# Sche_Boost.net
KiCad netlist of a schematic drawn in Altium Designer
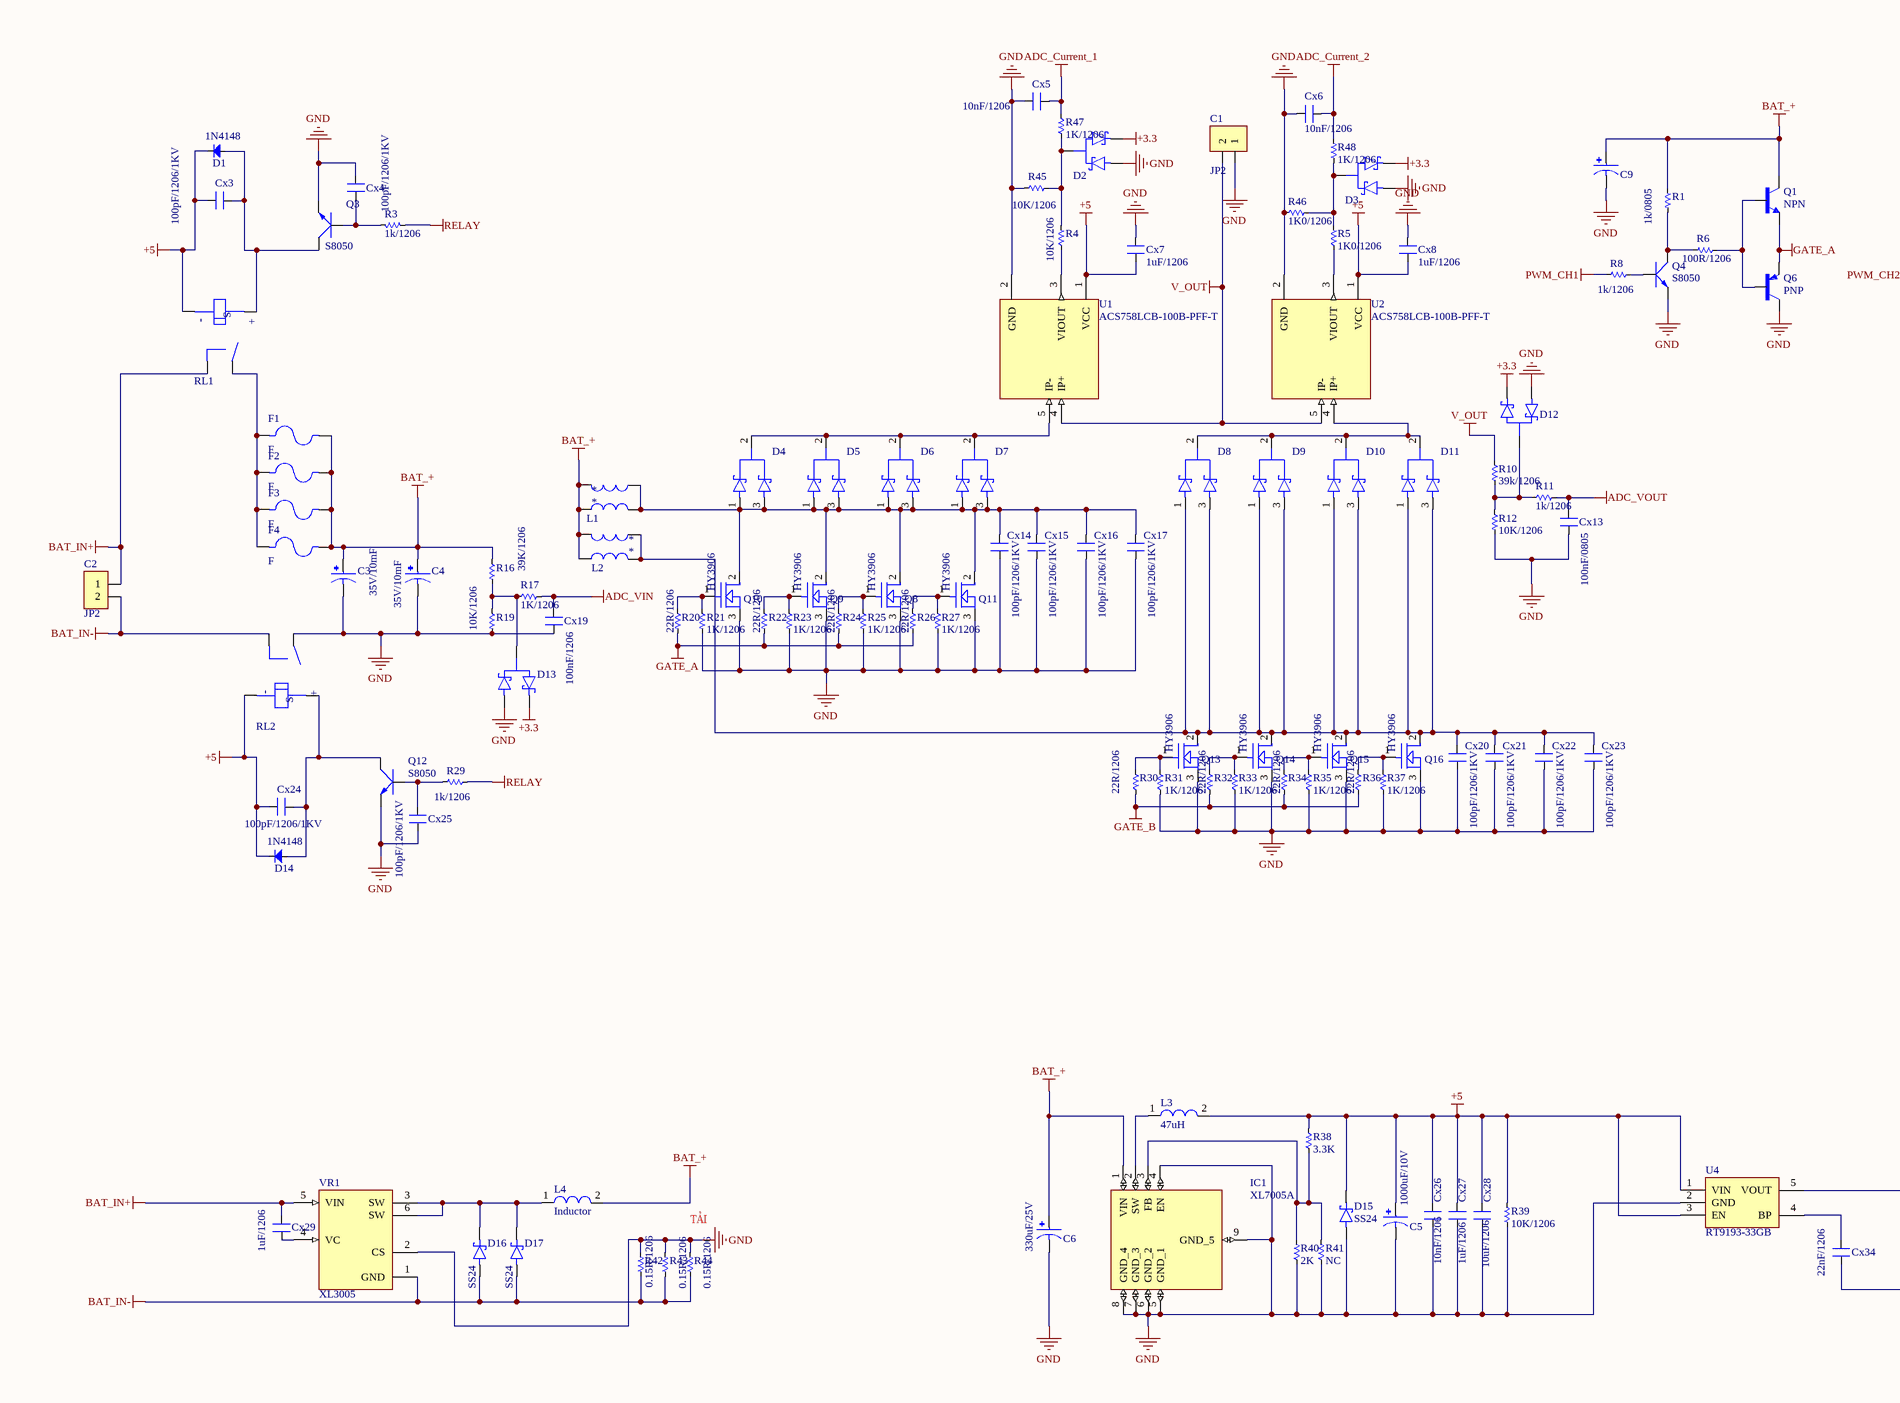
[diagram p0: Sche_Boost.SchDoc, left]
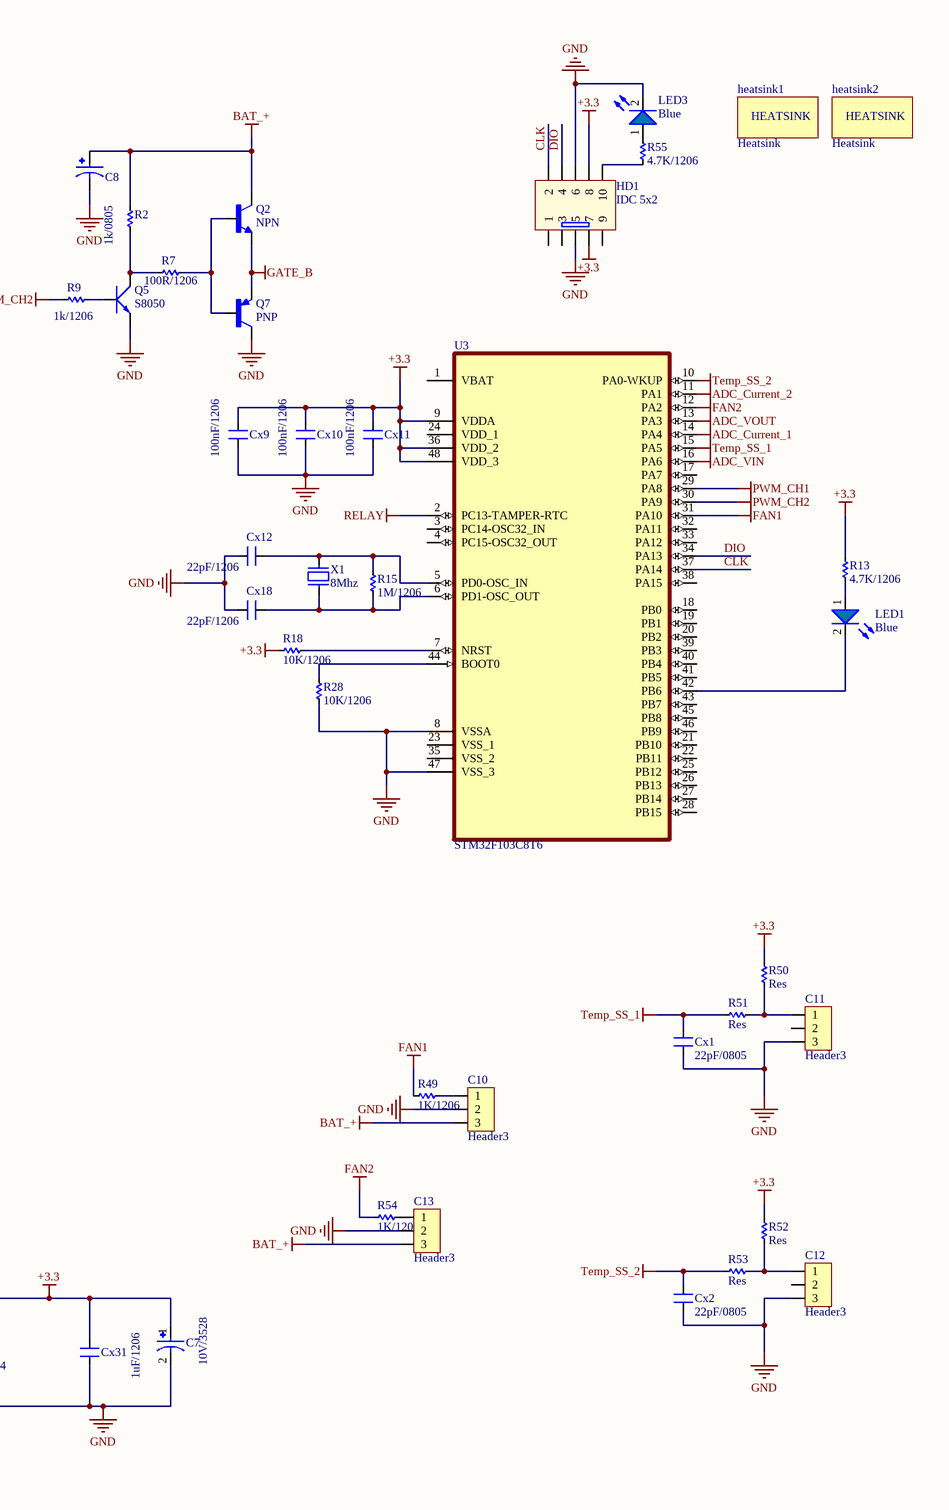
[diagram p1: Sche_Boost.SchDoc, right]

(export (version "E")
  (design (tool "Eeschema 10.0.6"))
  (components
    (comp (ref "C1")
      (value "JP2")
      (footprint "JACK_DC_120A")
      (description "WR-PHD 2.54 mm Angled Socket Header")
      (fields
        (field (name "MANUFACTURER") "Würth Elektronik eiSos GmbH")
        (field (name "PARTNO") "613002143121")
        (field (name "CREATED BY") "Karrer Zheng")
      )
      (libsource (lib "") (part "JP2_1"))
    )
    (comp (ref "C2")
      (value "JP2")
      (footprint "JACK_DC_120A")
      (description "WR-PHD 2.54 mm Angled Socket Header")
      (fields
        (field (name "MANUFACTURER") "Würth Elektronik eiSos GmbH")
        (field (name "PARTNO") "613002143121")
        (field (name "CREATED BY") "Karrer Zheng")
      )
      (libsource (lib "TechMT.VN_Lib_Project v2") (part "JP2"))
    )
    (comp (ref "C3")
      (value "35V/10mF")
      (footprint "cAP-ALU-30x30mm")
      (fields (field (name "PUBLISHER") "Altium Limited"))
      (libsource (lib "mySche") (part "CAP-ALU-DIP"))
    )
    (comp (ref "C4")
      (value "35V/10mF")
      (footprint "cAP-ALU-30x30mm")
      (fields (field (name "PUBLISHER") "Altium Limited"))
      (libsource (lib "mySche") (part "CAP-ALU-DIP"))
    )
    (comp (ref "C5")
      (value "1000uF/10V")
      (footprint "Cap Alu 8x12mm")
      (description "https://linhkienchatluong.vn/tu-nhom---tu-hoa-dan/tu-nhom-10v-1000uf-8x10mm_sp455_ct956.aspx")
      (fields (field (name "MF") "Panasonic") (field (name "DIGI-KEY_PART_NUMBER") "10-EEE-FN1A101URCT-ND"))
      (libsource (lib "mySche") (part "Cap Alu"))
    )
    (comp (ref "C6")
      (value "330uF/25V")
      (footprint "Cap Alu 8x12mm")
      (description "https://linhkienchatluong.vn/tu-nhom---tu-hoa-dan/tu-nhom-25v-330uf-8x10mm_sp455_ct971.aspx")
      (fields (field (name "MF") "Panasonic") (field (name "DIGI-KEY_PART_NUMBER") "10-EEE-FN1A101URCT-ND"))
      (libsource (lib "mySche") (part "Cap Alu"))
    )
    (comp (ref "C7")
      (value "10V/3528")
      (footprint "TANTALUM 3528")
      (fields (field (name "MP") "T493C106K020BH6310") (field (name "MF") "Kemet"))
      (libsource (lib "mySche") (part "Cap Tantalum"))
    )
    (comp (ref "C8")
      (value "Cap")
      (footprint "Cap Alu 5.0x5.4mm")
      (description "CAP ALU SMD")
      (fields (field (name "MF") "Panasonic") (field (name "DIGI-KEY_PART_NUMBER") "10-EEE-FN1A101URCT-ND"))
      (libsource (lib "mySche") (part "Cap Alu"))
    )
    (comp (ref "C9")
      (value "Cap")
      (footprint "Cap Alu 5.0x5.4mm")
      (description "CAP ALU SMD")
      (fields (field (name "MF") "Panasonic") (field (name "DIGI-KEY_PART_NUMBER") "10-EEE-FN1A101URCT-ND"))
      (libsource (lib "mySche") (part "Cap Alu"))
    )
    (comp (ref "C10")
      (value "Header3")
      (footprint "Header3")
      (fields
        (field (name "MANUFACTURER") "Würth Elektronik eiSos GmbH")
        (field (name "PARTNO") "613002143121")
        (field (name "CREATED BY") "Karrer Zheng")
      )
      (libsource (lib "TechMT.VN_Lib_Project v2") (part "Header3"))
    )
    (comp (ref "C11")
      (value "Header3")
      (footprint "Header3")
      (fields
        (field (name "MANUFACTURER") "Würth Elektronik eiSos GmbH")
        (field (name "PARTNO") "613002143121")
        (field (name "CREATED BY") "Karrer Zheng")
      )
      (libsource (lib "TechMT.VN_Lib_Project v2") (part "Header3"))
    )
    (comp (ref "C12")
      (value "Header3")
      (footprint "Header3")
      (fields
        (field (name "MANUFACTURER") "Würth Elektronik eiSos GmbH")
        (field (name "PARTNO") "613002143121")
        (field (name "CREATED BY") "Karrer Zheng")
      )
      (libsource (lib "TechMT.VN_Lib_Project v2") (part "Header3"))
    )
    (comp (ref "C13")
      (value "Header3")
      (footprint "Header3")
      (fields
        (field (name "MANUFACTURER") "Würth Elektronik eiSos GmbH")
        (field (name "PARTNO") "613002143121")
        (field (name "CREATED BY") "Karrer Zheng")
      )
      (libsource (lib "TechMT.VN_Lib_Project v2") (part "Header3"))
    )
    (comp (ref "Cx1")
      (value "22pF/0805")
      (footprint "CN-SMD-1206")
      (libsource (lib "TechMT.VN_Lib_Project v2") (part "CN"))
    )
    (comp (ref "Cx2")
      (value "22pF/0805")
      (footprint "CN-SMD-1206")
      (libsource (lib "TechMT.VN_Lib_Project v2") (part "CN"))
    )
    (comp (ref "Cx3")
      (value "100pF/1206/1KV")
      (footprint "CN-SMD-1206")
      (libsource (lib "TechMT.VN_Lib_Project v2") (part "CN"))
    )
    (comp (ref "Cx4")
      (value "100pF/1206/1KV")
      (footprint "CN-SMD-0805")
      (libsource (lib "TechMT.VN_Lib_Project v2") (part "CN"))
    )
    (comp (ref "Cx5")
      (value "10nF/1206")
      (footprint "CN-SMD-1206")
      (libsource (lib "TechMT.VN_Lib_Project v2") (part "CN"))
    )
    (comp (ref "Cx6")
      (value "10nF/1206")
      (footprint "CN-SMD-1206")
      (libsource (lib "TechMT.VN_Lib_Project v2") (part "CN"))
    )
    (comp (ref "Cx7")
      (value "1uF/1206")
      (footprint "CN-SMD-1206")
      (libsource (lib "TechMT.VN_Lib_Project v2") (part "CN"))
    )
    (comp (ref "Cx8")
      (value "1uF/1206")
      (footprint "CN-SMD-1206")
      (libsource (lib "TechMT.VN_Lib_Project v2") (part "CN"))
    )
    (comp (ref "Cx9")
      (value "100nF/1206")
      (footprint "CN-SMD-1206")
      (libsource (lib "TechMT.VN_Lib_Project v2") (part "CN"))
    )
    (comp (ref "Cx10")
      (value "100nF/1206")
      (footprint "CN-SMD-1206")
      (libsource (lib "TechMT.VN_Lib_Project v2") (part "CN"))
    )
    (comp (ref "Cx11")
      (value "100nF/1206")
      (footprint "CN-SMD-1206")
      (libsource (lib "TechMT.VN_Lib_Project v2") (part "CN"))
    )
    (comp (ref "Cx12")
      (value "22pF/1206")
      (footprint "CN-SMD-1206")
      (libsource (lib "TechMT.VN_Lib_Project v2") (part "CN"))
    )
    (comp (ref "Cx13")
      (value "100nF/0805")
      (footprint "CN-SMD-1206")
      (libsource (lib "TechMT.VN_Lib_Project v2") (part "CN"))
    )
    (comp (ref "Cx14")
      (value "100pF/1206/1KV")
      (footprint "CN-SMD-1206")
      (libsource (lib "TechMT.VN_Lib_Project v2") (part "CN"))
    )
    (comp (ref "Cx15")
      (value "100pF/1206/1KV")
      (footprint "CN-SMD-1206")
      (libsource (lib "TechMT.VN_Lib_Project v2") (part "CN"))
    )
    (comp (ref "Cx16")
      (value "100pF/1206/1KV")
      (footprint "CN-SMD-1206")
      (libsource (lib "TechMT.VN_Lib_Project v2") (part "CN"))
    )
    (comp (ref "Cx17")
      (value "100pF/1206/1KV")
      (footprint "CN-SMD-1206")
      (libsource (lib "TechMT.VN_Lib_Project v2") (part "CN"))
    )
    (comp (ref "Cx18")
      (value "22pF/1206")
      (footprint "CN-SMD-1206")
      (libsource (lib "TechMT.VN_Lib_Project v2") (part "CN"))
    )
    (comp (ref "Cx19")
      (value "100nF/1206")
      (footprint "CN-SMD-1206")
      (libsource (lib "TechMT.VN_Lib_Project v2") (part "CN"))
    )
    (comp (ref "Cx20")
      (value "100pF/1206/1KV")
      (footprint "CN-SMD-1206")
      (libsource (lib "TechMT.VN_Lib_Project v2") (part "CN"))
    )
    (comp (ref "Cx21")
      (value "100pF/1206/1KV")
      (footprint "CN-SMD-1206")
      (libsource (lib "TechMT.VN_Lib_Project v2") (part "CN"))
    )
    (comp (ref "Cx22")
      (value "100pF/1206/1KV")
      (footprint "CN-SMD-1206")
      (libsource (lib "TechMT.VN_Lib_Project v2") (part "CN"))
    )
    (comp (ref "Cx23")
      (value "100pF/1206/1KV")
      (footprint "CN-SMD-1206")
      (libsource (lib "TechMT.VN_Lib_Project v2") (part "CN"))
    )
    (comp (ref "Cx24")
      (value "100pF/1206/1KV")
      (footprint "CN-SMD-1206")
      (libsource (lib "TechMT.VN_Lib_Project v2") (part "CN"))
    )
    (comp (ref "Cx25")
      (value "100pF/1206/1KV")
      (footprint "CN-SMD-0805")
      (libsource (lib "TechMT.VN_Lib_Project v2") (part "CN"))
    )
    (comp (ref "Cx26")
      (value "10nF/1206")
      (footprint "CN-SMD-1206")
      (libsource (lib "TechMT.VN_Lib_Project v2") (part "CN"))
    )
    (comp (ref "Cx27")
      (value "1uF/1206")
      (footprint "CN-SMD-1206")
      (libsource (lib "TechMT.VN_Lib_Project v2") (part "CN"))
    )
    (comp (ref "Cx28")
      (value "10uF/1206")
      (footprint "CN-SMD-1206")
      (libsource (lib "TechMT.VN_Lib_Project v2") (part "CN"))
    )
    (comp (ref "Cx29")
      (value "1uF/1206")
      (footprint "CN-SMD-0805")
      (libsource (lib "TechMT.VN_Lib_Project v2") (part "CN"))
    )
    (comp (ref "Cx31")
      (value "1uF/1206")
      (footprint "CN-SMD-1206")
      (libsource (lib "TechMT.VN_Lib_Project v2") (part "CN"))
    )
    (comp (ref "Cx34")
      (value "22nF/1206")
      (footprint "CN-SMD-1206")
      (libsource (lib "TechMT.VN_Lib_Project v2") (part "CN"))
    )
    (comp (ref "D1")
      (value "1N4148")
      (footprint "1N4148_SMD")
      (description "Default Diode")
      (fields (field (name "PUBLISHER") "Altium Limited"))
      (libsource (lib "mySche") (part "Diode"))
    )
    (comp (ref "D2")
      (value "10A/200V")
      (footprint "SOT23-3-2-1-BCE")
      (description "Diode Dual Serial")
      (libsource (lib "mySche") (part "Diode Dual Serial"))
    )
    (comp (ref "D3")
      (value "10A/200V")
      (footprint "SOT23-3-2-1-BCE")
      (description "Diode Dual Serial")
      (libsource (lib "mySche") (part "Diode Dual Serial"))
    )
    (comp (ref "D4")
      (value "Diode schottky")
      (footprint "TO-220")
      (fields (field (name "MP") "MBRF20200CT"))
      (libsource (lib "mySche") (part "MBRF20200CT"))
    )
    (comp (ref "D5")
      (value "Diode schottky")
      (footprint "TO-220")
      (fields (field (name "MP") "MBRF20200CT"))
      (libsource (lib "mySche") (part "MBRF20200CT"))
    )
    (comp (ref "D6")
      (value "Diode schottky")
      (footprint "TO-220")
      (fields (field (name "MP") "MBRF20200CT"))
      (libsource (lib "mySche") (part "MBRF20200CT"))
    )
    (comp (ref "D7")
      (value "Diode schottky")
      (footprint "TO-220")
      (fields (field (name "MP") "MBRF20200CT"))
      (libsource (lib "mySche") (part "MBRF20200CT"))
    )
    (comp (ref "D8")
      (value "Diode schottky")
      (footprint "TO-220")
      (fields (field (name "MP") "MBRF20200CT"))
      (libsource (lib "mySche") (part "MBRF20200CT"))
    )
    (comp (ref "D9")
      (value "Diode schottky")
      (footprint "TO-220")
      (fields (field (name "MP") "MBRF20200CT"))
      (libsource (lib "mySche") (part "MBRF20200CT"))
    )
    (comp (ref "D10")
      (value "Diode schottky")
      (footprint "TO-220")
      (fields (field (name "MP") "MBRF20200CT"))
      (libsource (lib "mySche") (part "MBRF20200CT"))
    )
    (comp (ref "D11")
      (value "Diode schottky")
      (footprint "TO-220")
      (fields (field (name "MP") "MBRF20200CT"))
      (libsource (lib "mySche") (part "MBRF20200CT"))
    )
    (comp (ref "D12")
      (value "10A/200V")
      (footprint "SOT23-3-2-1-BCE")
      (description "Diode Dual Serial")
      (libsource (lib "mySche") (part "Diode Dual Serial"))
    )
    (comp (ref "D13")
      (value "BAV99")
      (footprint "SOT23-3-2-1-BCE")
      (description "Diode Dual Serial")
      (libsource (lib "mySche") (part "Diode Dual Serial"))
    )
    (comp (ref "D14")
      (value "1N4148")
      (footprint "1N4148_SMD")
      (description "Default Diode")
      (fields (field (name "PUBLISHER") "Altium Limited"))
      (libsource (lib "mySche") (part "Diode"))
    )
    (comp (ref "D15")
      (value "SS24")
      (footprint "SS24")
      (description "Diode Schottky 40V 2A Surface Mount DO-214AA (SMB)")
      (fields (field (name "MF") "ON Semiconductor"))
      (libsource (lib "mySche") (part "SS24"))
    )
    (comp (ref "D16")
      (value "SS24")
      (footprint "SS24")
      (description "Diode Schottky 40V 2A Surface Mount DO-214AA (SMB)")
      (fields (field (name "MF") "ON Semiconductor"))
      (libsource (lib "mySche") (part "SS24"))
    )
    (comp (ref "D17")
      (value "SS24")
      (footprint "SS24")
      (description "Diode Schottky 40V 2A Surface Mount DO-214AA (SMB)")
      (fields (field (name "MF") "ON Semiconductor"))
      (libsource (lib "mySche") (part "SS24"))
    )
    (comp (ref "F1")
      (value "F")
      (footprint "FUSE-Blade")
      (description "FUSE 20x5")
      (libsource (lib "mySche") (part "FUSE 20x5"))
    )
    (comp (ref "F2")
      (value "F")
      (footprint "FUSE-Blade")
      (description "FUSE 20x5")
      (libsource (lib "mySche") (part "FUSE 20x5"))
    )
    (comp (ref "F3")
      (value "F")
      (footprint "FUSE-Blade")
      (description "FUSE 20x5")
      (libsource (lib "mySche") (part "FUSE 20x5"))
    )
    (comp (ref "F4")
      (value "F")
      (footprint "FUSE-Blade")
      (description "FUSE 20x5")
      (libsource (lib "mySche") (part "FUSE 20x5"))
    )
    (comp (ref "HD1")
      (value "IDC 5x2")
      (footprint "IDC10")
      (libsource (lib "TechMT.VN_Lib_Project v2") (part "IDC 5X2"))
    )
    (comp (ref "heatsink1")
      (value "Heatsink")
      (footprint "HeatSink_200x47mm")
      (libsource (lib "lib") (part "Heatsink"))
    )
    (comp (ref "heatsink2")
      (value "Heatsink")
      (footprint "HeatSink_200x47mm")
      (libsource (lib "lib") (part "Heatsink"))
    )
    (comp (ref "IC1")
      (value "XL7005A")
      (footprint "SOIC127P600X175-9N")
      (description "https://snapeda.s3.amazonaws.com/datasheet/XL7005A_datasheet-English.pdf")
      (fields (field (name "MF") "XLSEMI"))
      (libsource (lib "mySche") (part "XL7005A"))
    )
    (comp (ref "L1")
      (value "coupled inductor")
      (footprint "L-DIP-2CORE-BRANCH")
      (libsource (lib "lib") (part "coupled inductor"))
    )
    (comp (ref "L2")
      (value "coupled inductor")
      (footprint "L-DIP-2CORE-BRANCH")
      (libsource (lib "") (part "coupled inductor_1"))
    )
    (comp (ref "L3") (value "47uH") (footprint "L-SMD-IRON") (libsource (lib "mySche") (part "Inductor_SMD")))
    (comp (ref "L4")
      (value "Inductor")
      (footprint "Inductor 10mmx10mm")
      (fields
        (field (name "MANUFACTURER_PART_NUMBER") "CDRH104RNP-100NC")
        (field (name "MOUSER PART NUMBER") "851-CDRH104RNP-100NC")
      )
      (libsource (lib "mySche") (part "Inductor"))
    )
    (comp (ref "LED1")
      (value "Blue")
      (footprint "LED-0805-Blue")
      (description "LED Blue 10mA 2.2v")
      (fields (field (name "Comment") "LED-Blue"))
      (libsource (lib "TechMT.VN_Lib_Project v2") (part "LED-Blue"))
    )
    (comp (ref "LED3")
      (value "Blue")
      (footprint "LED-0805-Blue")
      (description "LED Blue 10mA 2.2v")
      (fields (field (name "Comment") "4.7K/1206"))
      (libsource (lib "TechMT.VN_Lib_Project v2") (part "LED-Blue"))
    )
    (comp (ref "Q1")
      (value "NPN")
      (footprint "SOT89")
      (description "TRANSISTOR NPN")
      (fields (field (name "MP") "MJD31") (field (name "MF") "Motorola"))
      (libsource (lib "mySche") (part "TRANSISTOR NPN"))
    )
    (comp (ref "Q2")
      (value "NPN")
      (footprint "SOT89")
      (description "TRANSISTOR NPN")
      (fields (field (name "MP") "MJD31") (field (name "MF") "Motorola"))
      (libsource (lib "mySche") (part "TRANSISTOR NPN"))
    )
    (comp (ref "Q3")
      (value "S8050")
      (footprint "SOT23-3-2-1-BCE")
      (description "NPN 600mW, ECB")
      (libsource (lib "mySche") (part "S8050"))
    )
    (comp (ref "Q4")
      (value "S8050")
      (footprint "SOT23-3-2-1-BCE")
      (description "NPN 600mW, ECB")
      (libsource (lib "mySche") (part "S8050"))
    )
    (comp (ref "Q5")
      (value "S8050")
      (footprint "SOT23-3-2-1-BCE")
      (description "NPN 600mW, ECB")
      (libsource (lib "mySche") (part "S8050"))
    )
    (comp (ref "Q6")
      (value "PNP")
      (footprint "SOT89")
      (description "TRANSISTOR PNP")
      (fields (field (name "MP") "MJD31") (field (name "MF") "Motorola"))
      (libsource (lib "mySche") (part "TRANSISTOR PNP"))
    )
    (comp (ref "Q7")
      (value "PNP")
      (footprint "SOT89")
      (description "TRANSISTOR PNP")
      (fields (field (name "MP") "MJD31") (field (name "MF") "Motorola"))
      (libsource (lib "mySche") (part "TRANSISTOR PNP"))
    )
    (comp (ref "Q8")
      (value "HY3906")
      (footprint "TO-220-Tamgiac")
      (description "60V/150A")
      (libsource (lib "RAL") (part "MOSFET N"))
    )
    (comp (ref "Q9")
      (value "HY3906")
      (footprint "TO-220-Tamgiac")
      (description "60V/150A")
      (libsource (lib "RAL") (part "MOSFET N"))
    )
    (comp (ref "Q10")
      (value "HY3906")
      (footprint "TO-220-Tamgiac")
      (description "60V/150A")
      (libsource (lib "RAL") (part "MOSFET N"))
    )
    (comp (ref "Q11")
      (value "HY3906")
      (footprint "TO-220-Tamgiac")
      (description "60V/150A")
      (libsource (lib "RAL") (part "MOSFET N"))
    )
    (comp (ref "Q12")
      (value "S8050")
      (footprint "SOT23-3-2-1-BCE")
      (description "NPN 600mW, ECB")
      (libsource (lib "mySche") (part "S8050"))
    )
    (comp (ref "Q13")
      (value "HY3906")
      (footprint "TO-220-Tamgiac")
      (description "60V/150A")
      (libsource (lib "RAL") (part "MOSFET N"))
    )
    (comp (ref "Q14")
      (value "HY3906")
      (footprint "TO-220-Tamgiac")
      (description "60V/150A")
      (libsource (lib "RAL") (part "MOSFET N"))
    )
    (comp (ref "Q15")
      (value "HY3906")
      (footprint "TO-220-Tamgiac")
      (description "60V/150A")
      (libsource (lib "RAL") (part "MOSFET N"))
    )
    (comp (ref "Q16")
      (value "HY3906")
      (footprint "TO-220-Tamgiac")
      (description "60V/150A")
      (libsource (lib "RAL") (part "MOSFET N"))
    )
    (comp (ref "R1")
      (value "1k/0805")
      (footprint "RES-SMD-1206")
      (description "Resistor")
      (fields
        (field (name "MANUFACTURER") "Generic Components")
        (field (name "PUBLISHER") "Altium Hobart Technology Centre")
      )
      (libsource (lib "TechMT.VN_Lib_Project v2") (part "Res-SMD"))
    )
    (comp (ref "R2")
      (value "1k/0805")
      (footprint "RES-SMD-1206")
      (description "Resistor")
      (fields
        (field (name "MANUFACTURER") "Generic Components")
        (field (name "PUBLISHER") "Altium Hobart Technology Centre")
      )
      (libsource (lib "TechMT.VN_Lib_Project v2") (part "Res-SMD"))
    )
    (comp (ref "R3")
      (value "1k/1206")
      (footprint "RES-SMD-1206")
      (description "Resistor")
      (fields
        (field (name "MANUFACTURER") "Generic Components")
        (field (name "PUBLISHER") "Altium Hobart Technology Centre")
      )
      (libsource (lib "TechMT.VN_Lib_Project v2") (part "Res-SMD"))
    )
    (comp (ref "R4")
      (value "10K/1206")
      (footprint "RES-SMD-1206")
      (description "Resistor")
      (fields
        (field (name "MANUFACTURER") "Generic Components")
        (field (name "PUBLISHER") "Altium Hobart Technology Centre")
      )
      (libsource (lib "TechMT.VN_Lib_Project v2") (part "Res-SMD"))
    )
    (comp (ref "R5")
      (value "1K0/1206")
      (footprint "RES-SMD-1206")
      (description "Resistor")
      (fields
        (field (name "MANUFACTURER") "Generic Components")
        (field (name "PUBLISHER") "Altium Hobart Technology Centre")
      )
      (libsource (lib "TechMT.VN_Lib_Project v2") (part "Res-SMD"))
    )
    (comp (ref "R6")
      (value "100R/1206")
      (footprint "RES-SMD-1206")
      (description "Resistor")
      (fields
        (field (name "MANUFACTURER") "Generic Components")
        (field (name "PUBLISHER") "Altium Hobart Technology Centre")
      )
      (libsource (lib "TechMT.VN_Lib_Project v2") (part "Res-SMD"))
    )
    (comp (ref "R7")
      (value "100R/1206")
      (footprint "RES-SMD-1206")
      (description "Resistor")
      (fields
        (field (name "MANUFACTURER") "Generic Components")
        (field (name "PUBLISHER") "Altium Hobart Technology Centre")
      )
      (libsource (lib "TechMT.VN_Lib_Project v2") (part "Res-SMD"))
    )
    (comp (ref "R8")
      (value "1k/1206")
      (footprint "RES-SMD-1206")
      (description "Resistor")
      (fields
        (field (name "MANUFACTURER") "Generic Components")
        (field (name "PUBLISHER") "Altium Hobart Technology Centre")
      )
      (libsource (lib "TechMT.VN_Lib_Project v2") (part "Res-SMD"))
    )
    (comp (ref "R9")
      (value "1k/1206")
      (footprint "RES-SMD-1206")
      (description "Resistor")
      (fields
        (field (name "MANUFACTURER") "Generic Components")
        (field (name "PUBLISHER") "Altium Hobart Technology Centre")
      )
      (libsource (lib "TechMT.VN_Lib_Project v2") (part "Res-SMD"))
    )
    (comp (ref "R10")
      (value "39k/1206")
      (footprint "RES-SMD-1206")
      (description "Resistor")
      (fields
        (field (name "MANUFACTURER") "Generic Components")
        (field (name "PUBLISHER") "Altium Hobart Technology Centre")
      )
      (libsource (lib "TechMT.VN_Lib_Project v2") (part "Res-SMD"))
    )
    (comp (ref "R11")
      (value "1k/1206")
      (footprint "RES-SMD-1206")
      (description "Resistor")
      (fields
        (field (name "MANUFACTURER") "Generic Components")
        (field (name "PUBLISHER") "Altium Hobart Technology Centre")
      )
      (libsource (lib "TechMT.VN_Lib_Project v2") (part "Res-SMD"))
    )
    (comp (ref "R12")
      (value "10K/1206")
      (footprint "RES-SMD-1206")
      (description "Resistor")
      (fields
        (field (name "MANUFACTURER") "Generic Components")
        (field (name "PUBLISHER") "Altium Hobart Technology Centre")
      )
      (libsource (lib "TechMT.VN_Lib_Project v2") (part "Res-SMD"))
    )
    (comp (ref "R13")
      (value "4.7K/1206")
      (footprint "RES-SMD-1206")
      (description "Resistor")
      (fields
        (field (name "MANUFACTURER") "Generic Components")
        (field (name "PUBLISHER") "Altium Hobart Technology Centre")
      )
      (libsource (lib "TechMT.VN_Lib_Project v2") (part "Res-SMD"))
    )
    (comp (ref "R15")
      (value "1M/1206")
      (footprint "RES-SMD-1206")
      (fields
        (field (name "MANUFACTURER") "Generic Components")
        (field (name "PUBLISHER") "Altium Hobart Technology Centre")
      )
      (libsource (lib "TechMT.VN_Lib_Project v2") (part "Res-SMD"))
    )
    (comp (ref "R16")
      (value "39K/1206")
      (footprint "RES-SMD-1206")
      (description "Resistor")
      (fields
        (field (name "MANUFACTURER") "Generic Components")
        (field (name "PUBLISHER") "Altium Hobart Technology Centre")
      )
      (libsource (lib "TechMT.VN_Lib_Project v2") (part "Res-SMD"))
    )
    (comp (ref "R17")
      (value "1K/1206")
      (footprint "RES-SMD-1206")
      (description "Resistor")
      (fields
        (field (name "MANUFACTURER") "Generic Components")
        (field (name "PUBLISHER") "Altium Hobart Technology Centre")
      )
      (libsource (lib "TechMT.VN_Lib_Project v2") (part "Res-SMD"))
    )
    (comp (ref "R18")
      (value "10K/1206")
      (footprint "RES-SMD-1206")
      (fields
        (field (name "MANUFACTURER") "Generic Components")
        (field (name "PUBLISHER") "Altium Hobart Technology Centre")
      )
      (libsource (lib "TechMT.VN_Lib_Project v2") (part "Res-SMD"))
    )
    (comp (ref "R19")
      (value "10K/1206")
      (footprint "RES-SMD-1206")
      (fields
        (field (name "MANUFACTURER") "Generic Components")
        (field (name "PUBLISHER") "Altium Hobart Technology Centre")
      )
      (libsource (lib "TechMT.VN_Lib_Project v2") (part "Res-SMD"))
    )
    (comp (ref "R20")
      (value "22R/1206")
      (footprint "RES-SMD-1206")
      (description "Resistor")
      (fields
        (field (name "MANUFACTURER") "Generic Components")
        (field (name "PUBLISHER") "Altium Hobart Technology Centre")
      )
      (libsource (lib "TechMT.VN_Lib_Project v2") (part "Res-SMD"))
    )
    (comp (ref "R21")
      (value "1K/1206")
      (footprint "RES-SMD-1206")
      (fields
        (field (name "MANUFACTURER") "Generic Components")
        (field (name "PUBLISHER") "Altium Hobart Technology Centre")
      )
      (libsource (lib "TechMT.VN_Lib_Project v2") (part "Res-SMD"))
    )
    (comp (ref "R22")
      (value "22R/1206")
      (footprint "RES-SMD-1206")
      (description "Resistor")
      (fields
        (field (name "MANUFACTURER") "Generic Components")
        (field (name "PUBLISHER") "Altium Hobart Technology Centre")
      )
      (libsource (lib "TechMT.VN_Lib_Project v2") (part "Res-SMD"))
    )
    (comp (ref "R23")
      (value "1K/1206")
      (footprint "RES-SMD-1206")
      (fields
        (field (name "MANUFACTURER") "Generic Components")
        (field (name "PUBLISHER") "Altium Hobart Technology Centre")
      )
      (libsource (lib "TechMT.VN_Lib_Project v2") (part "Res-SMD"))
    )
    (comp (ref "R24")
      (value "22R/1206")
      (footprint "RES-SMD-1206")
      (description "Resistor")
      (fields
        (field (name "MANUFACTURER") "Generic Components")
        (field (name "PUBLISHER") "Altium Hobart Technology Centre")
      )
      (libsource (lib "TechMT.VN_Lib_Project v2") (part "Res-SMD"))
    )
    (comp (ref "R25")
      (value "1K/1206")
      (footprint "RES-SMD-1206")
      (fields
        (field (name "MANUFACTURER") "Generic Components")
        (field (name "PUBLISHER") "Altium Hobart Technology Centre")
      )
      (libsource (lib "TechMT.VN_Lib_Project v2") (part "Res-SMD"))
    )
    (comp (ref "R26")
      (value "22R/1206")
      (footprint "RES-SMD-1206")
      (description "Resistor")
      (fields
        (field (name "MANUFACTURER") "Generic Components")
        (field (name "PUBLISHER") "Altium Hobart Technology Centre")
      )
      (libsource (lib "TechMT.VN_Lib_Project v2") (part "Res-SMD"))
    )
    (comp (ref "R27")
      (value "1K/1206")
      (footprint "RES-SMD-1206")
      (fields
        (field (name "MANUFACTURER") "Generic Components")
        (field (name "PUBLISHER") "Altium Hobart Technology Centre")
      )
      (libsource (lib "TechMT.VN_Lib_Project v2") (part "Res-SMD"))
    )
    (comp (ref "R28")
      (value "10K/1206")
      (footprint "RES-SMD-1206")
      (description "Resistor")
      (fields
        (field (name "MANUFACTURER") "Generic Components")
        (field (name "PUBLISHER") "Altium Hobart Technology Centre")
      )
      (libsource (lib "TechMT.VN_Lib_Project v2") (part "Res-SMD"))
    )
    (comp (ref "R29")
      (value "1k/1206")
      (footprint "RES-SMD-1206")
      (description "Resistor")
      (fields
        (field (name "MANUFACTURER") "Generic Components")
        (field (name "PUBLISHER") "Altium Hobart Technology Centre")
      )
      (libsource (lib "TechMT.VN_Lib_Project v2") (part "Res-SMD"))
    )
    (comp (ref "R30")
      (value "22R/1206")
      (footprint "RES-SMD-1206")
      (fields
        (field (name "MANUFACTURER") "Generic Components")
        (field (name "PUBLISHER") "Altium Hobart Technology Centre")
      )
      (libsource (lib "TechMT.VN_Lib_Project v2") (part "Res-SMD"))
    )
    (comp (ref "R31")
      (value "1K/1206")
      (footprint "RES-SMD-1206")
      (fields
        (field (name "MANUFACTURER") "Generic Components")
        (field (name "PUBLISHER") "Altium Hobart Technology Centre")
      )
      (libsource (lib "TechMT.VN_Lib_Project v2") (part "Res-SMD"))
    )
    (comp (ref "R32")
      (value "22R/1206")
      (footprint "RES-SMD-1206")
      (fields
        (field (name "MANUFACTURER") "Generic Components")
        (field (name "PUBLISHER") "Altium Hobart Technology Centre")
      )
      (libsource (lib "TechMT.VN_Lib_Project v2") (part "Res-SMD"))
    )
    (comp (ref "R33")
      (value "1K/1206")
      (footprint "RES-SMD-1206")
      (fields
        (field (name "MANUFACTURER") "Generic Components")
        (field (name "PUBLISHER") "Altium Hobart Technology Centre")
      )
      (libsource (lib "TechMT.VN_Lib_Project v2") (part "Res-SMD"))
    )
    (comp (ref "R34")
      (value "22R/1206")
      (footprint "RES-SMD-1206")
      (fields
        (field (name "MANUFACTURER") "Generic Components")
        (field (name "PUBLISHER") "Altium Hobart Technology Centre")
      )
      (libsource (lib "TechMT.VN_Lib_Project v2") (part "Res-SMD"))
    )
    (comp (ref "R35")
      (value "1K/1206")
      (footprint "RES-SMD-1206")
      (fields
        (field (name "MANUFACTURER") "Generic Components")
        (field (name "PUBLISHER") "Altium Hobart Technology Centre")
      )
      (libsource (lib "TechMT.VN_Lib_Project v2") (part "Res-SMD"))
    )
    (comp (ref "R36")
      (value "22R/1206")
      (footprint "RES-SMD-1206")
      (fields
        (field (name "MANUFACTURER") "Generic Components")
        (field (name "PUBLISHER") "Altium Hobart Technology Centre")
      )
      (libsource (lib "TechMT.VN_Lib_Project v2") (part "Res-SMD"))
    )
    (comp (ref "R37")
      (value "1K/1206")
      (footprint "RES-SMD-1206")
      (fields
        (field (name "MANUFACTURER") "Generic Components")
        (field (name "PUBLISHER") "Altium Hobart Technology Centre")
      )
      (libsource (lib "TechMT.VN_Lib_Project v2") (part "Res-SMD"))
    )
    (comp (ref "R38")
      (value "3.3K")
      (footprint "RES-SMD-1206")
      (description "Resistor")
      (fields
        (field (name "MANUFACTURER") "Generic Components")
        (field (name "PUBLISHER") "Altium Hobart Technology Centre")
      )
      (libsource (lib "TechMT.VN_Lib_Project v2") (part "Res-SMD"))
    )
    (comp (ref "R39")
      (value "10K/1206")
      (footprint "RES-SMD-1206")
      (description "Resistor")
      (fields
        (field (name "MANUFACTURER") "Generic Components")
        (field (name "PUBLISHER") "Altium Hobart Technology Centre")
      )
      (libsource (lib "TechMT.VN_Lib_Project v2") (part "Res-SMD"))
    )
    (comp (ref "R40")
      (value "2K")
      (footprint "RES-SMD-1206")
      (description "Resistor")
      (fields
        (field (name "MANUFACTURER") "Generic Components")
        (field (name "PUBLISHER") "Altium Hobart Technology Centre")
      )
      (libsource (lib "TechMT.VN_Lib_Project v2") (part "Res-SMD"))
    )
    (comp (ref "R41")
      (value "NC")
      (footprint "RES-SMD-1206")
      (description "Resistor")
      (fields
        (field (name "MANUFACTURER") "Generic Components")
        (field (name "PUBLISHER") "Altium Hobart Technology Centre")
      )
      (libsource (lib "TechMT.VN_Lib_Project v2") (part "Res-SMD"))
    )
    (comp (ref "R42")
      (value "0.15R/1206")
      (footprint "RES-SMD-1206")
      (description "Resistor")
      (fields
        (field (name "MANUFACTURER") "Generic Components")
        (field (name "PUBLISHER") "Altium Hobart Technology Centre")
      )
      (libsource (lib "TechMT.VN_Lib_Project v2") (part "Res-SMD"))
    )
    (comp (ref "R43")
      (value "0.15R/1206")
      (footprint "RES-SMD-1206")
      (description "Resistor")
      (fields
        (field (name "MANUFACTURER") "Generic Components")
        (field (name "PUBLISHER") "Altium Hobart Technology Centre")
      )
      (libsource (lib "TechMT.VN_Lib_Project v2") (part "Res-SMD"))
    )
    (comp (ref "R44")
      (value "0.15R/1206")
      (footprint "RES-SMD-1206")
      (description "Resistor")
      (fields
        (field (name "MANUFACTURER") "Generic Components")
        (field (name "PUBLISHER") "Altium Hobart Technology Centre")
      )
      (libsource (lib "TechMT.VN_Lib_Project v2") (part "Res-SMD"))
    )
    (comp (ref "R45")
      (value "10K/1206")
      (footprint "RES-SMD-1206")
      (description "Resistor")
      (fields
        (field (name "MANUFACTURER") "Generic Components")
        (field (name "PUBLISHER") "Altium Hobart Technology Centre")
      )
      (libsource (lib "TechMT.VN_Lib_Project v2") (part "Res-SMD"))
    )
    (comp (ref "R46")
      (value "1K0/1206")
      (footprint "RES-SMD-1206")
      (description "Resistor")
      (fields
        (field (name "MANUFACTURER") "Generic Components")
        (field (name "PUBLISHER") "Altium Hobart Technology Centre")
      )
      (libsource (lib "TechMT.VN_Lib_Project v2") (part "Res-SMD"))
    )
    (comp (ref "R47")
      (value "1K/1206")
      (footprint "RES-SMD-1206")
      (description "Resistor")
      (fields
        (field (name "MANUFACTURER") "Generic Components")
        (field (name "PUBLISHER") "Altium Hobart Technology Centre")
      )
      (libsource (lib "TechMT.VN_Lib_Project v2") (part "Res-SMD"))
    )
    (comp (ref "R48")
      (value "1K/1206")
      (footprint "RES-SMD-1206")
      (description "Resistor")
      (fields
        (field (name "MANUFACTURER") "Generic Components")
        (field (name "PUBLISHER") "Altium Hobart Technology Centre")
      )
      (libsource (lib "TechMT.VN_Lib_Project v2") (part "Res-SMD"))
    )
    (comp (ref "R49")
      (value "1K/1206")
      (footprint "RES-SMD-1206")
      (description "Resistor")
      (fields
        (field (name "MANUFACTURER") "Generic Components")
        (field (name "PUBLISHER") "Altium Hobart Technology Centre")
      )
      (libsource (lib "TechMT.VN_Lib_Project v2") (part "Res-SMD"))
    )
    (comp (ref "R50")
      (value "Res")
      (footprint "RES-SMD-1206")
      (description "Resistor")
      (fields
        (field (name "MANUFACTURER") "Generic Components")
        (field (name "PUBLISHER") "Altium Hobart Technology Centre")
      )
      (libsource (lib "TechMT.VN_Lib_Project v2") (part "Res-SMD"))
    )
    (comp (ref "R51")
      (value "Res")
      (footprint "RES-SMD-1206")
      (description "Resistor")
      (fields
        (field (name "MANUFACTURER") "Generic Components")
        (field (name "PUBLISHER") "Altium Hobart Technology Centre")
      )
      (libsource (lib "TechMT.VN_Lib_Project v2") (part "Res-SMD"))
    )
    (comp (ref "R52")
      (value "Res")
      (footprint "RES-SMD-1206")
      (description "Resistor")
      (fields
        (field (name "MANUFACTURER") "Generic Components")
        (field (name "PUBLISHER") "Altium Hobart Technology Centre")
      )
      (libsource (lib "TechMT.VN_Lib_Project v2") (part "Res-SMD"))
    )
    (comp (ref "R53")
      (value "Res")
      (footprint "RES-SMD-1206")
      (description "Resistor")
      (fields
        (field (name "MANUFACTURER") "Generic Components")
        (field (name "PUBLISHER") "Altium Hobart Technology Centre")
      )
      (libsource (lib "TechMT.VN_Lib_Project v2") (part "Res-SMD"))
    )
    (comp (ref "R54")
      (value "1K/1206")
      (footprint "RES-SMD-1206")
      (description "Resistor")
      (fields
        (field (name "MANUFACTURER") "Generic Components")
        (field (name "PUBLISHER") "Altium Hobart Technology Centre")
      )
      (libsource (lib "TechMT.VN_Lib_Project v2") (part "Res-SMD"))
    )
    (comp (ref "R55")
      (value "4.7K/1206")
      (footprint "RES-SMD-1206")
      (description "Resistor")
      (fields
        (field (name "MANUFACTURER") "Generic Components")
        (field (name "PUBLISHER") "Altium Hobart Technology Centre")
      )
      (libsource (lib "TechMT.VN_Lib_Project v2") (part "Res-SMD"))
    )
    (comp (ref "RL1")
      (value "Relay YL-368-A")
      (footprint "Relay YL368-A")
      (libsource (lib "mySche") (part "Relay YL-368-A"))
    )
    (comp (ref "RL2")
      (value "Relay YL-368-A")
      (footprint "Relay YL368-A")
      (libsource (lib "mySche") (part "Relay YL-368-A"))
    )
    (comp (ref "U1")
      (value "ACS758LCB-100B-PFF-T")
      (footprint "ACS578xx")
      (description "Current Sensor 100A 1 Channel Hall Effect, Open Loop Bidirectional 5-CB Formed Leads, PFF")
      (fields (field (name "MF") "Allegro"))
      (libsource (lib "mySche") (part "ACS758LCB-100B-PFF-T"))
    )
    (comp (ref "U2")
      (value "ACS758LCB-100B-PFF-T")
      (footprint "ACS578xx")
      (description "Current Sensor 100A 1 Channel Hall Effect, Open Loop Bidirectional 5-CB Formed Leads, PFF")
      (fields (field (name "MF") "Allegro"))
      (libsource (lib "mySche") (part "ACS758LCB-100B-PFF-T"))
    )
    (comp (ref "U3")
      (value "STM32F103C8T6")
      (footprint "QFP50P900X900X160-48N")
      (description "ARMÂ® CortexÂ®-M3 STM32F1 Microcontroller IC 32-Bit 72MHz 64KB _64K x 8_ FLASH 48-LQFP _7x7_")
      (fields (field (name "MF") "STMicroelectronics") (field (name "MP") "STM32F103C8T7"))
      (libsource (lib "lib") (part "STM32F103C8T7"))
    )
    (comp (ref "U4")
      (value "RT9193-33GB")
      (footprint "SOT94P279X129-5N")
      (description "Linear Voltage Regulator IC Positive Fixed 1 Output 300mA TSOT-23-5")
      (fields (field (name "MF") "Richtek USA") (field (name "DIGI-KEY_PART_NUMBER") "1028-1014-2-ND"))
      (libsource (lib "mySche") (part "RT9193-33GB"))
    )
    (comp (ref "VR1")
      (value "XL3005")
      (footprint "TO-263_L")
      (fields (field (name "MF") "XLSEMI") (field (name "MP") "XL6009"))
      (libsource (lib "mySche") (part "XL3005"))
    )
    (comp (ref "X1")
      (value "8Mhz")
      (footprint "XT2")
      (description "Crystal, 32.768 KHz, -40 to 85 degC, 3.2 x 1.5 x 0.9 mm SMD")
      (libsource (lib "RAL") (part "XT2"))
    )
  )
  (nets
    (net (code "1") (name "+3.3") (class "Default")
      (node (ref "C7") (pin "1") (pinfunction "1_1") (pintype "passive"))
      (node (ref "Cx10") (pin "2") (pinfunction "2_2") (pintype "passive"))
      (node (ref "Cx11") (pin "2") (pinfunction "2_2") (pintype "passive"))
      (node (ref "Cx31") (pin "2") (pinfunction "2_2") (pintype "passive"))
      (node (ref "Cx9") (pin "2") (pinfunction "2_2") (pintype "passive"))
      (node (ref "D12") (pin "2") (pinfunction "A_2") (pintype "passive"))
      (node (ref "D13") (pin "2") (pinfunction "A_2") (pintype "passive"))
      (node (ref "D2") (pin "2") (pinfunction "A_2") (pintype "passive"))
      (node (ref "D3") (pin "2") (pinfunction "A_2") (pintype "passive"))
      (node (ref "HD1") (pin "7") (pinfunction "7_7") (pintype "passive"))
      (node (ref "HD1") (pin "8") (pinfunction "8_8") (pintype "passive"))
      (node (ref "R13") (pin "2") (pinfunction "2_2") (pintype "passive"))
      (node (ref "R18") (pin "2") (pinfunction "2_2") (pintype "passive"))
      (node (ref "R50") (pin "2") (pinfunction "2_2") (pintype "passive"))
      (node (ref "R52") (pin "2") (pinfunction "2_2") (pintype "passive"))
      (node (ref "U3") (pin "36") (pinfunction "VDD_2_36") (pintype "power_in"))
      (node (ref "U3") (pin "48") (pinfunction "VDD_3_48") (pintype "power_in"))
      (node (ref "U3") (pin "9") (pinfunction "VDDA_9") (pintype "power_in"))
      (node (ref "U4") (pin "5") (pinfunction "VOUT_5") (pintype "passive"))
    )
    (net (code "2") (name "+5") (class "Default")
      (node (ref "C5") (pin "1") (pinfunction "1_1") (pintype "passive"))
      (node (ref "Cx24") (pin "2") (pinfunction "2_2") (pintype "passive"))
      (node (ref "Cx26") (pin "2") (pinfunction "2_2") (pintype "passive"))
      (node (ref "Cx27") (pin "2") (pinfunction "2_2") (pintype "passive"))
      (node (ref "Cx28") (pin "2") (pinfunction "2_2") (pintype "passive"))
      (node (ref "Cx3") (pin "2") (pinfunction "2_2") (pintype "passive"))
      (node (ref "Cx7") (pin "2") (pinfunction "2_2") (pintype "passive"))
      (node (ref "Cx8") (pin "2") (pinfunction "2_2") (pintype "passive"))
      (node (ref "D1") (pin "2") (pinfunction "K_2") (pintype "passive"))
      (node (ref "D14") (pin "2") (pinfunction "K_2") (pintype "passive"))
      (node (ref "D15") (pin "2") (pinfunction "K_2") (pintype "passive"))
      (node (ref "L3") (pin "2") (pinfunction "2_2") (pintype "passive"))
      (node (ref "R38") (pin "1") (pinfunction "1_1") (pintype "passive"))
      (node (ref "R39") (pin "1") (pinfunction "1_1") (pintype "passive"))
      (node (ref "RL1") (pin "2") (pinfunction "2_2") (pintype "passive"))
      (node (ref "RL2") (pin "2") (pinfunction "2_2") (pintype "passive"))
      (node (ref "U1") (pin "1") (pinfunction "VCC_1") (pintype "power_in"))
      (node (ref "U2") (pin "1") (pinfunction "VCC_1") (pintype "power_in"))
      (node (ref "U4") (pin "1") (pinfunction "VIN_1") (pintype "passive"))
      (node (ref "U4") (pin "3") (pinfunction "EN_3") (pintype "passive"))
    )
    (net (code "3") (name "/CLK") (class "Default")
      (node (ref "HD1") (pin "2") (pinfunction "2_2") (pintype "passive"))
      (node (ref "U3") (pin "37") (pinfunction "PA14_37") (pintype "bidirectional"))
    )
    (net (code "4") (name "/DIO") (class "Default")
      (node (ref "HD1") (pin "4") (pinfunction "4_4") (pintype "passive"))
      (node (ref "U3") (pin "34") (pinfunction "PA13_34") (pintype "bidirectional"))
    )
    (net (code "5") (name "ADC_Current_1") (class "Default")
      (node (ref "Cx5") (pin "2") (pinfunction "2_2") (pintype "passive"))
      (node (ref "R47") (pin "1") (pinfunction "1_1") (pintype "passive"))
      (node (ref "U3") (pin "14") (pinfunction "PA4_14") (pintype "bidirectional"))
    )
    (net (code "6") (name "ADC_Current_2") (class "Default")
      (node (ref "Cx6") (pin "2") (pinfunction "2_2") (pintype "passive"))
      (node (ref "R48") (pin "1") (pinfunction "1_1") (pintype "passive"))
      (node (ref "U3") (pin "11") (pinfunction "PA1_11") (pintype "bidirectional"))
    )
    (net (code "7") (name "ADC_VIN") (class "Default")
      (node (ref "Cx19") (pin "1") (pinfunction "1_1") (pintype "passive"))
      (node (ref "R17") (pin "1") (pinfunction "1_1") (pintype "passive"))
      (node (ref "U3") (pin "16") (pinfunction "PA6_16") (pintype "bidirectional"))
    )
    (net (code "8") (name "ADC_VOUT") (class "Default")
      (node (ref "Cx13") (pin "1") (pinfunction "1_1") (pintype "passive"))
      (node (ref "R11") (pin "1") (pinfunction "1_1") (pintype "passive"))
      (node (ref "U3") (pin "13") (pinfunction "PA3_13") (pintype "bidirectional"))
    )
    (net (code "9") (name "BAT_+") (class "Default")
      (node (ref "C10") (pin "3") (pinfunction "3_3") (pintype "passive"))
      (node (ref "C13") (pin "3") (pinfunction "3_3") (pintype "passive"))
      (node (ref "C3") (pin "1") (pinfunction "1_1") (pintype "passive"))
      (node (ref "C4") (pin "1") (pinfunction "1_1") (pintype "passive"))
      (node (ref "C6") (pin "1") (pinfunction "1_1") (pintype "passive"))
      (node (ref "C8") (pin "1") (pinfunction "1_1") (pintype "passive"))
      (node (ref "C9") (pin "1") (pinfunction "1_1") (pintype "passive"))
      (node (ref "F1") (pin "2") (pinfunction "2_2") (pintype "passive"))
      (node (ref "F2") (pin "2") (pinfunction "2_2") (pintype "passive"))
      (node (ref "F3") (pin "2") (pinfunction "2_2") (pintype "passive"))
      (node (ref "F4") (pin "2") (pinfunction "2_2") (pintype "passive"))
      (node (ref "IC1") (pin "1") (pinfunction "VIN_1") (pintype "bidirectional"))
      (node (ref "L1") (pin "3") (pinfunction "3_3") (pintype "passive"))
      (node (ref "L1") (pin "4") (pinfunction "4_4") (pintype "passive"))
      (node (ref "L2") (pin "1") (pinfunction "1_1") (pintype "passive"))
      (node (ref "L2") (pin "2") (pinfunction "2_2") (pintype "passive"))
      (node (ref "L4") (pin "2") (pinfunction "2_2") (pintype "passive"))
      (node (ref "Q1") (pin "2") (pinfunction "C_2") (pintype "passive"))
      (node (ref "Q2") (pin "2") (pinfunction "C_2") (pintype "passive"))
      (node (ref "R1") (pin "2") (pinfunction "2_2") (pintype "passive"))
      (node (ref "R16") (pin "2") (pinfunction "2_2") (pintype "passive"))
      (node (ref "R2") (pin "2") (pinfunction "2_2") (pintype "passive"))
    )
    (net (code "10") (name "BAT_IN+") (class "Default")
      (node (ref "C2") (pin "1") (pinfunction "1_1") (pintype "passive"))
      (node (ref "Cx29") (pin "2") (pinfunction "2_2") (pintype "passive"))
      (node (ref "RL1") (pin "3") (pinfunction "3_3") (pintype "passive"))
      (node (ref "VR1") (pin "5") (pinfunction "VIN_5") (pintype "input"))
    )
    (net (code "11") (name "BAT_IN-") (class "Default")
      (node (ref "C2") (pin "2") (pinfunction "2_2") (pintype "passive"))
      (node (ref "D16") (pin "1") (pinfunction "A_1") (pintype "passive"))
      (node (ref "D17") (pin "1") (pinfunction "A_1") (pintype "passive"))
      (node (ref "R42") (pin "2") (pinfunction "2_2") (pintype "passive"))
      (node (ref "R43") (pin "2") (pinfunction "2_2") (pintype "passive"))
      (node (ref "R44") (pin "2") (pinfunction "2_2") (pintype "passive"))
      (node (ref "RL2") (pin "3") (pinfunction "3_3") (pintype "passive"))
      (node (ref "VR1") (pin "1") (pinfunction "GND_1") (pintype "power_in"))
    )
    (net (code "12") (name "FAN1") (class "Default")
      (node (ref "R49") (pin "1") (pinfunction "1_1") (pintype "passive"))
      (node (ref "U3") (pin "31") (pinfunction "PA10_31") (pintype "bidirectional"))
    )
    (net (code "13") (name "FAN2") (class "Default")
      (node (ref "R54") (pin "1") (pinfunction "1_1") (pintype "passive"))
      (node (ref "U3") (pin "12") (pinfunction "PA2_12") (pintype "bidirectional"))
    )
    (net (code "14") (name "GATE_A") (class "Default")
      (node (ref "Q1") (pin "3") (pinfunction "E_3") (pintype "passive"))
      (node (ref "Q6") (pin "3") (pinfunction "E_3") (pintype "passive"))
      (node (ref "R20") (pin "1") (pinfunction "1_1") (pintype "passive"))
      (node (ref "R22") (pin "1") (pinfunction "1_1") (pintype "passive"))
      (node (ref "R24") (pin "1") (pinfunction "1_1") (pintype "passive"))
      (node (ref "R26") (pin "1") (pinfunction "1_1") (pintype "passive"))
    )
    (net (code "15") (name "GATE_B") (class "Default")
      (node (ref "Q2") (pin "3") (pinfunction "E_3") (pintype "passive"))
      (node (ref "Q7") (pin "3") (pinfunction "E_3") (pintype "passive"))
      (node (ref "R30") (pin "1") (pinfunction "1_1") (pintype "passive"))
      (node (ref "R32") (pin "1") (pinfunction "1_1") (pintype "passive"))
      (node (ref "R34") (pin "1") (pinfunction "1_1") (pintype "passive"))
      (node (ref "R36") (pin "1") (pinfunction "1_1") (pintype "passive"))
    )
    (net (code "16") (name "GND") (class "Default")
      (node (ref "C1") (pin "1") (pinfunction "1_1") (pintype "passive"))
      (node (ref "C10") (pin "2") (pinfunction "2_2") (pintype "passive"))
      (node (ref "C11") (pin "3") (pinfunction "3_3") (pintype "passive"))
      (node (ref "C12") (pin "3") (pinfunction "3_3") (pintype "passive"))
      (node (ref "C13") (pin "2") (pinfunction "2_2") (pintype "passive"))
      (node (ref "C3") (pin "2") (pinfunction "2_2") (pintype "passive"))
      (node (ref "C4") (pin "2") (pinfunction "2_2") (pintype "passive"))
      (node (ref "C5") (pin "2") (pinfunction "2_2") (pintype "passive"))
      (node (ref "C6") (pin "2") (pinfunction "2_2") (pintype "passive"))
      (node (ref "C7") (pin "2") (pinfunction "2_2") (pintype "passive"))
      (node (ref "C8") (pin "2") (pinfunction "2_2") (pintype "passive"))
      (node (ref "C9") (pin "2") (pinfunction "2_2") (pintype "passive"))
      (node (ref "Cx1") (pin "2") (pinfunction "2_2") (pintype "passive"))
      (node (ref "Cx10") (pin "1") (pinfunction "1_1") (pintype "passive"))
      (node (ref "Cx11") (pin "1") (pinfunction "1_1") (pintype "passive"))
      (node (ref "Cx12") (pin "2") (pinfunction "2_2") (pintype "passive"))
      (node (ref "Cx13") (pin "2") (pinfunction "2_2") (pintype "passive"))
      (node (ref "Cx14") (pin "1") (pinfunction "1_1") (pintype "passive"))
      (node (ref "Cx15") (pin "1") (pinfunction "1_1") (pintype "passive"))
      (node (ref "Cx16") (pin "1") (pinfunction "1_1") (pintype "passive"))
      (node (ref "Cx17") (pin "1") (pinfunction "1_1") (pintype "passive"))
      (node (ref "Cx18") (pin "2") (pinfunction "2_2") (pintype "passive"))
      (node (ref "Cx19") (pin "2") (pinfunction "2_2") (pintype "passive"))
      (node (ref "Cx2") (pin "2") (pinfunction "2_2") (pintype "passive"))
      (node (ref "Cx20") (pin "1") (pinfunction "1_1") (pintype "passive"))
      (node (ref "Cx21") (pin "1") (pinfunction "1_1") (pintype "passive"))
      (node (ref "Cx22") (pin "1") (pinfunction "1_1") (pintype "passive"))
      (node (ref "Cx23") (pin "1") (pinfunction "1_1") (pintype "passive"))
      (node (ref "Cx25") (pin "2") (pinfunction "2_2") (pintype "passive"))
      (node (ref "Cx26") (pin "1") (pinfunction "1_1") (pintype "passive"))
      (node (ref "Cx27") (pin "1") (pinfunction "1_1") (pintype "passive"))
      (node (ref "Cx28") (pin "1") (pinfunction "1_1") (pintype "passive"))
      (node (ref "Cx31") (pin "1") (pinfunction "1_1") (pintype "passive"))
      (node (ref "Cx34") (pin "1") (pinfunction "1_1") (pintype "passive"))
      (node (ref "Cx4") (pin "2") (pinfunction "2_2") (pintype "passive"))
      (node (ref "Cx5") (pin "1") (pinfunction "1_1") (pintype "passive"))
      (node (ref "Cx6") (pin "1") (pinfunction "1_1") (pintype "passive"))
      (node (ref "Cx7") (pin "1") (pinfunction "1_1") (pintype "passive"))
      (node (ref "Cx8") (pin "1") (pinfunction "1_1") (pintype "passive"))
      (node (ref "Cx9") (pin "1") (pinfunction "1_1") (pintype "passive"))
      (node (ref "D12") (pin "1") (pinfunction "A_1") (pintype "passive"))
      (node (ref "D13") (pin "1") (pinfunction "A_1") (pintype "passive"))
      (node (ref "D15") (pin "1") (pinfunction "A_1") (pintype "passive"))
      (node (ref "D2") (pin "1") (pinfunction "A_1") (pintype "passive"))
      (node (ref "D3") (pin "1") (pinfunction "A_1") (pintype "passive"))
      (node (ref "HD1") (pin "5") (pinfunction "5_5") (pintype "passive"))
      (node (ref "HD1") (pin "6") (pinfunction "6_6") (pintype "passive"))
      (node (ref "IC1") (pin "4") (pinfunction "EN_4") (pintype "bidirectional"))
      (node (ref "IC1") (pin "5") (pinfunction "GND_1_5") (pintype "bidirectional"))
      (node (ref "IC1") (pin "6") (pinfunction "GND_2_6") (pintype "bidirectional"))
      (node (ref "IC1") (pin "7") (pinfunction "GND_3_7") (pintype "bidirectional"))
      (node (ref "IC1") (pin "8") (pinfunction "GND_4_8") (pintype "bidirectional"))
      (node (ref "IC1") (pin "9") (pinfunction "GND_5_9") (pintype "bidirectional"))
      (node (ref "LED3") (pin "2") (pinfunction "K_2") (pintype "passive"))
      (node (ref "Q10") (pin "3") (pinfunction "S_3") (pintype "passive"))
      (node (ref "Q11") (pin "3") (pinfunction "S_3") (pintype "passive"))
      (node (ref "Q12") (pin "1") (pinfunction "E_1") (pintype "passive"))
      (node (ref "Q13") (pin "3") (pinfunction "S_3") (pintype "passive"))
      (node (ref "Q14") (pin "3") (pinfunction "S_3") (pintype "passive"))
      (node (ref "Q15") (pin "3") (pinfunction "S_3") (pintype "passive"))
      (node (ref "Q16") (pin "3") (pinfunction "S_3") (pintype "passive"))
      (node (ref "Q3") (pin "1") (pinfunction "E_1") (pintype "passive"))
      (node (ref "Q4") (pin "1") (pinfunction "E_1") (pintype "passive"))
      (node (ref "Q5") (pin "1") (pinfunction "E_1") (pintype "passive"))
      (node (ref "Q6") (pin "2") (pinfunction "C_2") (pintype "passive"))
      (node (ref "Q7") (pin "2") (pinfunction "C_2") (pintype "passive"))
      (node (ref "Q8") (pin "3") (pinfunction "S_3") (pintype "passive"))
      (node (ref "Q9") (pin "3") (pinfunction "S_3") (pintype "passive"))
      (node (ref "R12") (pin "1") (pinfunction "1_1") (pintype "passive"))
      (node (ref "R19") (pin "1") (pinfunction "1_1") (pintype "passive"))
      (node (ref "R21") (pin "1") (pinfunction "1_1") (pintype "passive"))
      (node (ref "R23") (pin "1") (pinfunction "1_1") (pintype "passive"))
      (node (ref "R25") (pin "1") (pinfunction "1_1") (pintype "passive"))
      (node (ref "R27") (pin "1") (pinfunction "1_1") (pintype "passive"))
      (node (ref "R28") (pin "1") (pinfunction "1_1") (pintype "passive"))
      (node (ref "R31") (pin "1") (pinfunction "1_1") (pintype "passive"))
      (node (ref "R33") (pin "1") (pinfunction "1_1") (pintype "passive"))
      (node (ref "R35") (pin "1") (pinfunction "1_1") (pintype "passive"))
      (node (ref "R37") (pin "1") (pinfunction "1_1") (pintype "passive"))
      (node (ref "R39") (pin "2") (pinfunction "2_2") (pintype "passive"))
      (node (ref "R40") (pin "2") (pinfunction "2_2") (pintype "passive"))
      (node (ref "R41") (pin "2") (pinfunction "2_2") (pintype "passive"))
      (node (ref "R42") (pin "1") (pinfunction "1_1") (pintype "passive"))
      (node (ref "R43") (pin "1") (pinfunction "1_1") (pintype "passive"))
      (node (ref "R44") (pin "1") (pinfunction "1_1") (pintype "passive"))
      (node (ref "R45") (pin "2") (pinfunction "2_2") (pintype "passive"))
      (node (ref "R46") (pin "2") (pinfunction "2_2") (pintype "passive"))
      (node (ref "RL2") (pin "4") (pinfunction "4_4") (pintype "passive"))
      (node (ref "U1") (pin "2") (pinfunction "GND_2") (pintype "power_in"))
      (node (ref "U2") (pin "2") (pinfunction "GND_2") (pintype "power_in"))
      (node (ref "U3") (pin "47") (pinfunction "VSS_3_47") (pintype "passive"))
      (node (ref "U3") (pin "8") (pinfunction "VSSA_8") (pintype "passive"))
      (node (ref "U4") (pin "2") (pinfunction "GND_2") (pintype "power_in"))
      (node (ref "VR1") (pin "2") (pinfunction "CS_2") (pintype "passive"))
    )
    (net (code "17") (name "Net-(C10-Pad1)") (class "Default")
      (node (ref "C10") (pin "1") (pinfunction "1_1") (pintype "passive"))
      (node (ref "R49") (pin "2") (pinfunction "2_2") (pintype "passive"))
    )
    (net (code "18") (name "Net-(C11-Pad1)") (class "Default")
      (node (ref "C11") (pin "1") (pinfunction "1_1") (pintype "passive"))
      (node (ref "R50") (pin "1") (pinfunction "1_1") (pintype "passive"))
      (node (ref "R51") (pin "1") (pinfunction "1_1") (pintype "passive"))
    )
    (net (code "19") (name "Net-(C12-Pad1)") (class "Default")
      (node (ref "C12") (pin "1") (pinfunction "1_1") (pintype "passive"))
      (node (ref "R52") (pin "1") (pinfunction "1_1") (pintype "passive"))
      (node (ref "R53") (pin "1") (pinfunction "1_1") (pintype "passive"))
    )
    (net (code "20") (name "Net-(C13-Pad1)") (class "Default")
      (node (ref "C13") (pin "1") (pinfunction "1_1") (pintype "passive"))
      (node (ref "R54") (pin "2") (pinfunction "2_2") (pintype "passive"))
    )
    (net (code "21") (name "Net-(D1-A)") (class "Default")
      (node (ref "Cx3") (pin "1") (pinfunction "1_1") (pintype "passive"))
      (node (ref "D1") (pin "1") (pinfunction "A_1") (pintype "passive"))
      (node (ref "Q3") (pin "2") (pinfunction "C_2") (pintype "passive"))
      (node (ref "RL1") (pin "1") (pinfunction "1_1") (pintype "passive"))
    )
    (net (code "22") (name "Net-(D2-AK)") (class "Default")
      (node (ref "D2") (pin "3") (pinfunction "AK_3") (pintype "passive"))
      (node (ref "R4") (pin "2") (pinfunction "2_2") (pintype "passive"))
      (node (ref "R45") (pin "1") (pinfunction "1_1") (pintype "passive"))
      (node (ref "R47") (pin "2") (pinfunction "2_2") (pintype "passive"))
    )
    (net (code "23") (name "Net-(D3-AK)") (class "Default")
      (node (ref "D3") (pin "3") (pinfunction "AK_3") (pintype "passive"))
      (node (ref "R46") (pin "1") (pinfunction "1_1") (pintype "passive"))
      (node (ref "R48") (pin "2") (pinfunction "2_2") (pintype "passive"))
      (node (ref "R5") (pin "2") (pinfunction "2_2") (pintype "passive"))
    )
    (net (code "24") (name "Net-(D4-A1)") (class "Default")
      (node (ref "Cx14") (pin "2") (pinfunction "2_2") (pintype "passive"))
      (node (ref "Cx15") (pin "2") (pinfunction "2_2") (pintype "passive"))
      (node (ref "Cx16") (pin "2") (pinfunction "2_2") (pintype "passive"))
      (node (ref "Cx17") (pin "2") (pinfunction "2_2") (pintype "passive"))
      (node (ref "D4") (pin "1") (pinfunction "A1_1") (pintype "passive"))
      (node (ref "D4") (pin "3") (pinfunction "A3_3") (pintype "passive"))
      (node (ref "D5") (pin "1") (pinfunction "A1_1") (pintype "passive"))
      (node (ref "D5") (pin "3") (pinfunction "A3_3") (pintype "passive"))
      (node (ref "D6") (pin "1") (pinfunction "A1_1") (pintype "passive"))
      (node (ref "D6") (pin "3") (pinfunction "A3_3") (pintype "passive"))
      (node (ref "D7") (pin "1") (pinfunction "A1_1") (pintype "passive"))
      (node (ref "D7") (pin "3") (pinfunction "A3_3") (pintype "passive"))
      (node (ref "L1") (pin "1") (pinfunction "1_1") (pintype "passive"))
      (node (ref "L1") (pin "2") (pinfunction "2_2") (pintype "passive"))
      (node (ref "Q10") (pin "2") (pinfunction "D_2") (pintype "passive"))
      (node (ref "Q11") (pin "2") (pinfunction "D_2") (pintype "passive"))
      (node (ref "Q8") (pin "2") (pinfunction "D_2") (pintype "passive"))
      (node (ref "Q9") (pin "2") (pinfunction "D_2") (pintype "passive"))
    )
    (net (code "25") (name "Net-(D4-K)") (class "Default")
      (node (ref "D4") (pin "2") (pinfunction "K_2") (pintype "passive"))
      (node (ref "D5") (pin "2") (pinfunction "K_2") (pintype "passive"))
      (node (ref "D6") (pin "2") (pinfunction "K_2") (pintype "passive"))
      (node (ref "D7") (pin "2") (pinfunction "K_2") (pintype "passive"))
      (node (ref "U1") (pin "5") (pinfunction "IP-_5") (pintype "input"))
    )
    (net (code "26") (name "Net-(D10-A1)") (class "Default")
      (node (ref "Cx20") (pin "2") (pinfunction "2_2") (pintype "passive"))
      (node (ref "Cx21") (pin "2") (pinfunction "2_2") (pintype "passive"))
      (node (ref "Cx22") (pin "2") (pinfunction "2_2") (pintype "passive"))
      (node (ref "Cx23") (pin "2") (pinfunction "2_2") (pintype "passive"))
      (node (ref "D10") (pin "1") (pinfunction "A1_1") (pintype "passive"))
      (node (ref "D10") (pin "3") (pinfunction "A3_3") (pintype "passive"))
      (node (ref "D11") (pin "1") (pinfunction "A1_1") (pintype "passive"))
      (node (ref "D11") (pin "3") (pinfunction "A3_3") (pintype "passive"))
      (node (ref "D8") (pin "1") (pinfunction "A1_1") (pintype "passive"))
      (node (ref "D8") (pin "3") (pinfunction "A3_3") (pintype "passive"))
      (node (ref "D9") (pin "1") (pinfunction "A1_1") (pintype "passive"))
      (node (ref "D9") (pin "3") (pinfunction "A3_3") (pintype "passive"))
      (node (ref "L2") (pin "3") (pinfunction "3_3") (pintype "passive"))
      (node (ref "L2") (pin "4") (pinfunction "4_4") (pintype "passive"))
      (node (ref "Q13") (pin "2") (pinfunction "D_2") (pintype "passive"))
      (node (ref "Q14") (pin "2") (pinfunction "D_2") (pintype "passive"))
      (node (ref "Q15") (pin "2") (pinfunction "D_2") (pintype "passive"))
      (node (ref "Q16") (pin "2") (pinfunction "D_2") (pintype "passive"))
    )
    (net (code "27") (name "Net-(D10-K)") (class "Default")
      (node (ref "D10") (pin "2") (pinfunction "K_2") (pintype "passive"))
      (node (ref "D11") (pin "2") (pinfunction "K_2") (pintype "passive"))
      (node (ref "D8") (pin "2") (pinfunction "K_2") (pintype "passive"))
      (node (ref "D9") (pin "2") (pinfunction "K_2") (pintype "passive"))
      (node (ref "U2") (pin "4") (pinfunction "IP+_4") (pintype "input"))
    )
    (net (code "28") (name "Net-(D12-AK)") (class "Default")
      (node (ref "D12") (pin "3") (pinfunction "AK_3") (pintype "passive"))
      (node (ref "R10") (pin "1") (pinfunction "1_1") (pintype "passive"))
      (node (ref "R11") (pin "2") (pinfunction "2_2") (pintype "passive"))
      (node (ref "R12") (pin "2") (pinfunction "2_2") (pintype "passive"))
    )
    (net (code "29") (name "Net-(D13-AK)") (class "Default")
      (node (ref "D13") (pin "3") (pinfunction "AK_3") (pintype "passive"))
      (node (ref "R16") (pin "1") (pinfunction "1_1") (pintype "passive"))
      (node (ref "R17") (pin "2") (pinfunction "2_2") (pintype "passive"))
      (node (ref "R19") (pin "2") (pinfunction "2_2") (pintype "passive"))
    )
    (net (code "30") (name "Net-(D14-A)") (class "Default")
      (node (ref "Cx24") (pin "1") (pinfunction "1_1") (pintype "passive"))
      (node (ref "D14") (pin "1") (pinfunction "A_1") (pintype "passive"))
      (node (ref "Q12") (pin "2") (pinfunction "C_2") (pintype "passive"))
      (node (ref "RL2") (pin "1") (pinfunction "1_1") (pintype "passive"))
    )
    (net (code "31") (name "Net-(D16-K)") (class "Default")
      (node (ref "D16") (pin "2") (pinfunction "K_2") (pintype "passive"))
      (node (ref "D17") (pin "2") (pinfunction "K_2") (pintype "passive"))
      (node (ref "L4") (pin "1") (pinfunction "1_1") (pintype "passive"))
      (node (ref "VR1") (pin "3") (pinfunction "SW_3") (pintype "passive"))
      (node (ref "VR1") (pin "6") (pinfunction "SW_6") (pintype "passive"))
    )
    (net (code "32") (name "Net-(F1-Pad1)") (class "Default")
      (node (ref "F1") (pin "1") (pinfunction "1_1") (pintype "passive"))
      (node (ref "F2") (pin "1") (pinfunction "1_1") (pintype "passive"))
      (node (ref "F3") (pin "1") (pinfunction "1_1") (pintype "passive"))
      (node (ref "F4") (pin "1") (pinfunction "1_1") (pintype "passive"))
      (node (ref "RL1") (pin "4") (pinfunction "4_4") (pintype "passive"))
    )
    (net (code "33") (name "Net-(HD1-Pad10)") (class "Default")
      (node (ref "HD1") (pin "10") (pinfunction "10_10") (pintype "passive"))
      (node (ref "R55") (pin "2") (pinfunction "2_2") (pintype "passive"))
    )
    (net (code "34") (name "Net-(IC1-FB)") (class "Default")
      (node (ref "IC1") (pin "3") (pinfunction "FB_3") (pintype "bidirectional"))
      (node (ref "R38") (pin "2") (pinfunction "2_2") (pintype "passive"))
      (node (ref "R40") (pin "1") (pinfunction "1_1") (pintype "passive"))
      (node (ref "R41") (pin "1") (pinfunction "1_1") (pintype "passive"))
    )
    (net (code "35") (name "Net-(IC1-SW)") (class "Default")
      (node (ref "IC1") (pin "2") (pinfunction "SW_2") (pintype "bidirectional"))
      (node (ref "L3") (pin "1") (pinfunction "1_1") (pintype "passive"))
    )
    (net (code "36") (name "Net-(LED1-A)") (class "Default")
      (node (ref "LED1") (pin "1") (pinfunction "A_1") (pintype "passive"))
      (node (ref "R13") (pin "1") (pinfunction "1_1") (pintype "passive"))
    )
    (net (code "37") (name "Net-(LED1-K)") (class "Default")
      (node (ref "LED1") (pin "2") (pinfunction "K_2") (pintype "passive"))
      (node (ref "U3") (pin "42") (pinfunction "PB6_42") (pintype "bidirectional"))
    )
    (net (code "38") (name "Net-(LED3-A)") (class "Default")
      (node (ref "LED3") (pin "1") (pinfunction "A_1") (pintype "passive"))
      (node (ref "R55") (pin "1") (pinfunction "1_1") (pintype "passive"))
    )
    (net (code "39") (name "Net-(Q1-B)") (class "Default")
      (node (ref "Q1") (pin "1") (pinfunction "B_1") (pintype "passive"))
      (node (ref "Q6") (pin "1") (pinfunction "B_1") (pintype "passive"))
      (node (ref "R6") (pin "2") (pinfunction "2_2") (pintype "passive"))
    )
    (net (code "40") (name "Net-(Q2-B)") (class "Default")
      (node (ref "Q2") (pin "1") (pinfunction "B_1") (pintype "passive"))
      (node (ref "Q7") (pin "1") (pinfunction "B_1") (pintype "passive"))
      (node (ref "R7") (pin "2") (pinfunction "2_2") (pintype "passive"))
    )
    (net (code "41") (name "Net-(Q3-B)") (class "Default")
      (node (ref "Cx4") (pin "1") (pinfunction "1_1") (pintype "passive"))
      (node (ref "Q3") (pin "3") (pinfunction "B_3") (pintype "passive"))
      (node (ref "R3") (pin "1") (pinfunction "1_1") (pintype "passive"))
    )
    (net (code "42") (name "Net-(Q4-B)") (class "Default")
      (node (ref "Q4") (pin "3") (pinfunction "B_3") (pintype "passive"))
      (node (ref "R8") (pin "2") (pinfunction "2_2") (pintype "passive"))
    )
    (net (code "43") (name "Net-(Q4-C)") (class "Default")
      (node (ref "Q4") (pin "2") (pinfunction "C_2") (pintype "passive"))
      (node (ref "R1") (pin "1") (pinfunction "1_1") (pintype "passive"))
      (node (ref "R6") (pin "1") (pinfunction "1_1") (pintype "passive"))
    )
    (net (code "44") (name "Net-(Q5-B)") (class "Default")
      (node (ref "Q5") (pin "3") (pinfunction "B_3") (pintype "passive"))
      (node (ref "R9") (pin "2") (pinfunction "2_2") (pintype "passive"))
    )
    (net (code "45") (name "Net-(Q5-C)") (class "Default")
      (node (ref "Q5") (pin "2") (pinfunction "C_2") (pintype "passive"))
      (node (ref "R2") (pin "1") (pinfunction "1_1") (pintype "passive"))
      (node (ref "R7") (pin "1") (pinfunction "1_1") (pintype "passive"))
    )
    (net (code "46") (name "Net-(Q8-G)") (class "Default")
      (node (ref "Q8") (pin "1") (pinfunction "G_1") (pintype "passive"))
      (node (ref "R24") (pin "2") (pinfunction "2_2") (pintype "passive"))
      (node (ref "R25") (pin "2") (pinfunction "2_2") (pintype "passive"))
    )
    (net (code "47") (name "Net-(Q9-G)") (class "Default")
      (node (ref "Q9") (pin "1") (pinfunction "G_1") (pintype "passive"))
      (node (ref "R22") (pin "2") (pinfunction "2_2") (pintype "passive"))
      (node (ref "R23") (pin "2") (pinfunction "2_2") (pintype "passive"))
    )
    (net (code "48") (name "Net-(Q10-G)") (class "Default")
      (node (ref "Q10") (pin "1") (pinfunction "G_1") (pintype "passive"))
      (node (ref "R20") (pin "2") (pinfunction "2_2") (pintype "passive"))
      (node (ref "R21") (pin "2") (pinfunction "2_2") (pintype "passive"))
    )
    (net (code "49") (name "Net-(Q11-G)") (class "Default")
      (node (ref "Q11") (pin "1") (pinfunction "G_1") (pintype "passive"))
      (node (ref "R26") (pin "2") (pinfunction "2_2") (pintype "passive"))
      (node (ref "R27") (pin "2") (pinfunction "2_2") (pintype "passive"))
    )
    (net (code "50") (name "Net-(Q12-B)") (class "Default")
      (node (ref "Cx25") (pin "1") (pinfunction "1_1") (pintype "passive"))
      (node (ref "Q12") (pin "3") (pinfunction "B_3") (pintype "passive"))
      (node (ref "R29") (pin "1") (pinfunction "1_1") (pintype "passive"))
    )
    (net (code "51") (name "Net-(Q13-G)") (class "Default")
      (node (ref "Q13") (pin "1") (pinfunction "G_1") (pintype "passive"))
      (node (ref "R30") (pin "2") (pinfunction "2_2") (pintype "passive"))
      (node (ref "R31") (pin "2") (pinfunction "2_2") (pintype "passive"))
    )
    (net (code "52") (name "Net-(Q14-G)") (class "Default")
      (node (ref "Q14") (pin "1") (pinfunction "G_1") (pintype "passive"))
      (node (ref "R32") (pin "2") (pinfunction "2_2") (pintype "passive"))
      (node (ref "R33") (pin "2") (pinfunction "2_2") (pintype "passive"))
    )
    (net (code "53") (name "Net-(Q15-G)") (class "Default")
      (node (ref "Q15") (pin "1") (pinfunction "G_1") (pintype "passive"))
      (node (ref "R34") (pin "2") (pinfunction "2_2") (pintype "passive"))
      (node (ref "R35") (pin "2") (pinfunction "2_2") (pintype "passive"))
    )
    (net (code "54") (name "Net-(Q16-G)") (class "Default")
      (node (ref "Q16") (pin "1") (pinfunction "G_1") (pintype "passive"))
      (node (ref "R36") (pin "2") (pinfunction "2_2") (pintype "passive"))
      (node (ref "R37") (pin "2") (pinfunction "2_2") (pintype "passive"))
    )
    (net (code "55") (name "Net-(U1-VIOUT)") (class "Default")
      (node (ref "R4") (pin "1") (pinfunction "1_1") (pintype "passive"))
      (node (ref "U1") (pin "3") (pinfunction "VIOUT_3") (pintype "output"))
    )
    (net (code "56") (name "Net-(U2-VIOUT)") (class "Default")
      (node (ref "R5") (pin "1") (pinfunction "1_1") (pintype "passive"))
      (node (ref "U2") (pin "3") (pinfunction "VIOUT_3") (pintype "output"))
    )
    (net (code "57") (name "Net-(U3-BOOT0)") (class "Default")
      (node (ref "R28") (pin "2") (pinfunction "2_2") (pintype "passive"))
      (node (ref "U3") (pin "44") (pinfunction "BOOT0_44") (pintype "input"))
    )
    (net (code "58") (name "Net-(U3-NRST)") (class "Default")
      (node (ref "R18") (pin "1") (pinfunction "1_1") (pintype "passive"))
      (node (ref "U3") (pin "7") (pinfunction "NRST_7") (pintype "bidirectional"))
    )
    (net (code "59") (name "Net-(U3-PD0-OSC_IN)") (class "Default")
      (node (ref "Cx12") (pin "1") (pinfunction "1_1") (pintype "passive"))
      (node (ref "R15") (pin "1") (pinfunction "1_1") (pintype "passive"))
      (node (ref "U3") (pin "5") (pinfunction "PD0-OSC_IN_5") (pintype "bidirectional"))
      (node (ref "X1") (pin "1") (pinfunction "1_1") (pintype "passive"))
    )
    (net (code "60") (name "Net-(U3-PD1-OSC_OUT)") (class "Default")
      (node (ref "Cx18") (pin "1") (pinfunction "1_1") (pintype "passive"))
      (node (ref "R15") (pin "2") (pinfunction "2_2") (pintype "passive"))
      (node (ref "U3") (pin "6") (pinfunction "PD1-OSC_OUT_6") (pintype "bidirectional"))
      (node (ref "X1") (pin "2") (pinfunction "2_2") (pintype "passive"))
    )
    (net (code "61") (name "Net-(U4-BP)") (class "Default")
      (node (ref "Cx34") (pin "2") (pinfunction "2_2") (pintype "passive"))
      (node (ref "U4") (pin "4") (pinfunction "BP_4") (pintype "passive"))
    )
    (net (code "62") (name "Net-(VR1-VC)") (class "Default")
      (node (ref "Cx29") (pin "1") (pinfunction "1_1") (pintype "passive"))
      (node (ref "VR1") (pin "4") (pinfunction "VC_4") (pintype "input"))
    )
    (net (code "63") (name "PWM_CH1") (class "Default")
      (node (ref "R8") (pin "1") (pinfunction "1_1") (pintype "passive"))
      (node (ref "U3") (pin "29") (pinfunction "PA8_29") (pintype "bidirectional"))
    )
    (net (code "64") (name "PWM_CH2") (class "Default")
      (node (ref "R9") (pin "1") (pinfunction "1_1") (pintype "passive"))
      (node (ref "U3") (pin "30") (pinfunction "PA9_30") (pintype "bidirectional"))
    )
    (net (code "65") (name "RELAY") (class "Default")
      (node (ref "R29") (pin "2") (pinfunction "2_2") (pintype "passive"))
      (node (ref "R3") (pin "2") (pinfunction "2_2") (pintype "passive"))
      (node (ref "U3") (pin "2") (pinfunction "PC13-TAMPER-RTC_2") (pintype "bidirectional"))
    )
    (net (code "66") (name "Temp_SS_1") (class "Default")
      (node (ref "Cx1") (pin "1") (pinfunction "1_1") (pintype "passive"))
      (node (ref "R51") (pin "2") (pinfunction "2_2") (pintype "passive"))
      (node (ref "U3") (pin "15") (pinfunction "PA5_15") (pintype "bidirectional"))
    )
    (net (code "67") (name "Temp_SS_2") (class "Default")
      (node (ref "Cx2") (pin "1") (pinfunction "1_1") (pintype "passive"))
      (node (ref "R53") (pin "2") (pinfunction "2_2") (pintype "passive"))
      (node (ref "U3") (pin "10") (pinfunction "PA0-WKUP_10") (pintype "bidirectional"))
    )
    (net (code "68") (name "V_OUT") (class "Default")
      (node (ref "C1") (pin "2") (pinfunction "2_2") (pintype "passive"))
      (node (ref "R10") (pin "2") (pinfunction "2_2") (pintype "passive"))
      (node (ref "U1") (pin "4") (pinfunction "IP+_4") (pintype "input"))
      (node (ref "U2") (pin "5") (pinfunction "IP-_5") (pintype "input"))
    )
    (net (code "69") (name "unconnected-(C11-Pad2)") (class "Default")
      (node (ref "C11") (pin "2") (pinfunction "2_2") (pintype "passive"))
    )
    (net (code "70") (name "unconnected-(C12-Pad2)") (class "Default")
      (node (ref "C12") (pin "2") (pinfunction "2_2") (pintype "passive"))
    )
    (net (code "71") (name "unconnected-(HD1-Pad1)") (class "Default")
      (node (ref "HD1") (pin "1") (pinfunction "1_1") (pintype "passive"))
    )
    (net (code "72") (name "unconnected-(HD1-Pad3)") (class "Default")
      (node (ref "HD1") (pin "3") (pinfunction "3_3") (pintype "passive"))
    )
    (net (code "73") (name "unconnected-(HD1-Pad9)") (class "Default")
      (node (ref "HD1") (pin "9") (pinfunction "9_9") (pintype "passive"))
    )
    (net (code "74") (name "unconnected-(U3-PA7-Pad17)") (class "Default")
      (node (ref "U3") (pin "17") (pinfunction "PA7_17") (pintype "bidirectional"))
    )
    (net (code "75") (name "unconnected-(U3-PA11-Pad32)") (class "Default")
      (node (ref "U3") (pin "32") (pinfunction "PA11_32") (pintype "bidirectional"))
    )
    (net (code "76") (name "unconnected-(U3-PA12-Pad33)") (class "Default")
      (node (ref "U3") (pin "33") (pinfunction "PA12_33") (pintype "bidirectional"))
    )
    (net (code "77") (name "unconnected-(U3-PA15-Pad38)") (class "Default")
      (node (ref "U3") (pin "38") (pinfunction "PA15_38") (pintype "bidirectional"))
    )
    (net (code "78") (name "unconnected-(U3-PB0-Pad18)") (class "Default")
      (node (ref "U3") (pin "18") (pinfunction "PB0_18") (pintype "bidirectional"))
    )
    (net (code "79") (name "unconnected-(U3-PB1-Pad19)") (class "Default")
      (node (ref "U3") (pin "19") (pinfunction "PB1_19") (pintype "bidirectional"))
    )
    (net (code "80") (name "unconnected-(U3-PB2-Pad20)") (class "Default")
      (node (ref "U3") (pin "20") (pinfunction "PB2_20") (pintype "bidirectional"))
    )
    (net (code "81") (name "unconnected-(U3-PB3-Pad39)") (class "Default")
      (node (ref "U3") (pin "39") (pinfunction "PB3_39") (pintype "bidirectional"))
    )
    (net (code "82") (name "unconnected-(U3-PB4-Pad40)") (class "Default")
      (node (ref "U3") (pin "40") (pinfunction "PB4_40") (pintype "bidirectional"))
    )
    (net (code "83") (name "unconnected-(U3-PB5-Pad41)") (class "Default")
      (node (ref "U3") (pin "41") (pinfunction "PB5_41") (pintype "bidirectional"))
    )
    (net (code "84") (name "unconnected-(U3-PB7-Pad43)") (class "Default")
      (node (ref "U3") (pin "43") (pinfunction "PB7_43") (pintype "bidirectional"))
    )
    (net (code "85") (name "unconnected-(U3-PB8-Pad45)") (class "Default")
      (node (ref "U3") (pin "45") (pinfunction "PB8_45") (pintype "bidirectional"))
    )
    (net (code "86") (name "unconnected-(U3-PB9-Pad46)") (class "Default")
      (node (ref "U3") (pin "46") (pinfunction "PB9_46") (pintype "bidirectional"))
    )
    (net (code "87") (name "unconnected-(U3-PB10-Pad21)") (class "Default")
      (node (ref "U3") (pin "21") (pinfunction "PB10_21") (pintype "bidirectional"))
    )
    (net (code "88") (name "unconnected-(U3-PB11-Pad22)") (class "Default")
      (node (ref "U3") (pin "22") (pinfunction "PB11_22") (pintype "bidirectional"))
    )
    (net (code "89") (name "unconnected-(U3-PB12-Pad25)") (class "Default")
      (node (ref "U3") (pin "25") (pinfunction "PB12_25") (pintype "bidirectional"))
    )
    (net (code "90") (name "unconnected-(U3-PB13-Pad26)") (class "Default")
      (node (ref "U3") (pin "26") (pinfunction "PB13_26") (pintype "bidirectional"))
    )
    (net (code "91") (name "unconnected-(U3-PB14-Pad27)") (class "Default")
      (node (ref "U3") (pin "27") (pinfunction "PB14_27") (pintype "bidirectional"))
    )
    (net (code "92") (name "unconnected-(U3-PB15-Pad28)") (class "Default")
      (node (ref "U3") (pin "28") (pinfunction "PB15_28") (pintype "bidirectional"))
    )
    (net (code "93") (name "unconnected-(U3-PC14-OSC32_IN-Pad3)") (class "Default")
      (node (ref "U3") (pin "3") (pinfunction "PC14-OSC32_IN_3") (pintype "bidirectional"))
    )
    (net (code "94") (name "unconnected-(U3-PC15-OSC32_OUT-Pad4)") (class "Default")
      (node (ref "U3") (pin "4") (pinfunction "PC15-OSC32_OUT_4") (pintype "bidirectional"))
    )
    (net (code "95") (name "unconnected-(U3-VBAT-Pad1)") (class "Default")
      (node (ref "U3") (pin "1") (pinfunction "VBAT_1") (pintype "power_in"))
    )
    (net (code "96") (name "unconnected-(U3-VDD_1-Pad24)") (class "Default")
      (node (ref "U3") (pin "24") (pinfunction "VDD_1_24") (pintype "power_in"))
    )
    (net (code "97") (name "unconnected-(U3-VSS_1-Pad23)") (class "Default")
      (node (ref "U3") (pin "23") (pinfunction "VSS_1_23") (pintype "passive"))
    )
    (net (code "98") (name "unconnected-(U3-VSS_2-Pad35)") (class "Default")
      (node (ref "U3") (pin "35") (pinfunction "VSS_2_35") (pintype "passive"))
    )
  )
)
